# DotPhat.net
KiCad netlist of a schematic drawn in EAGLE
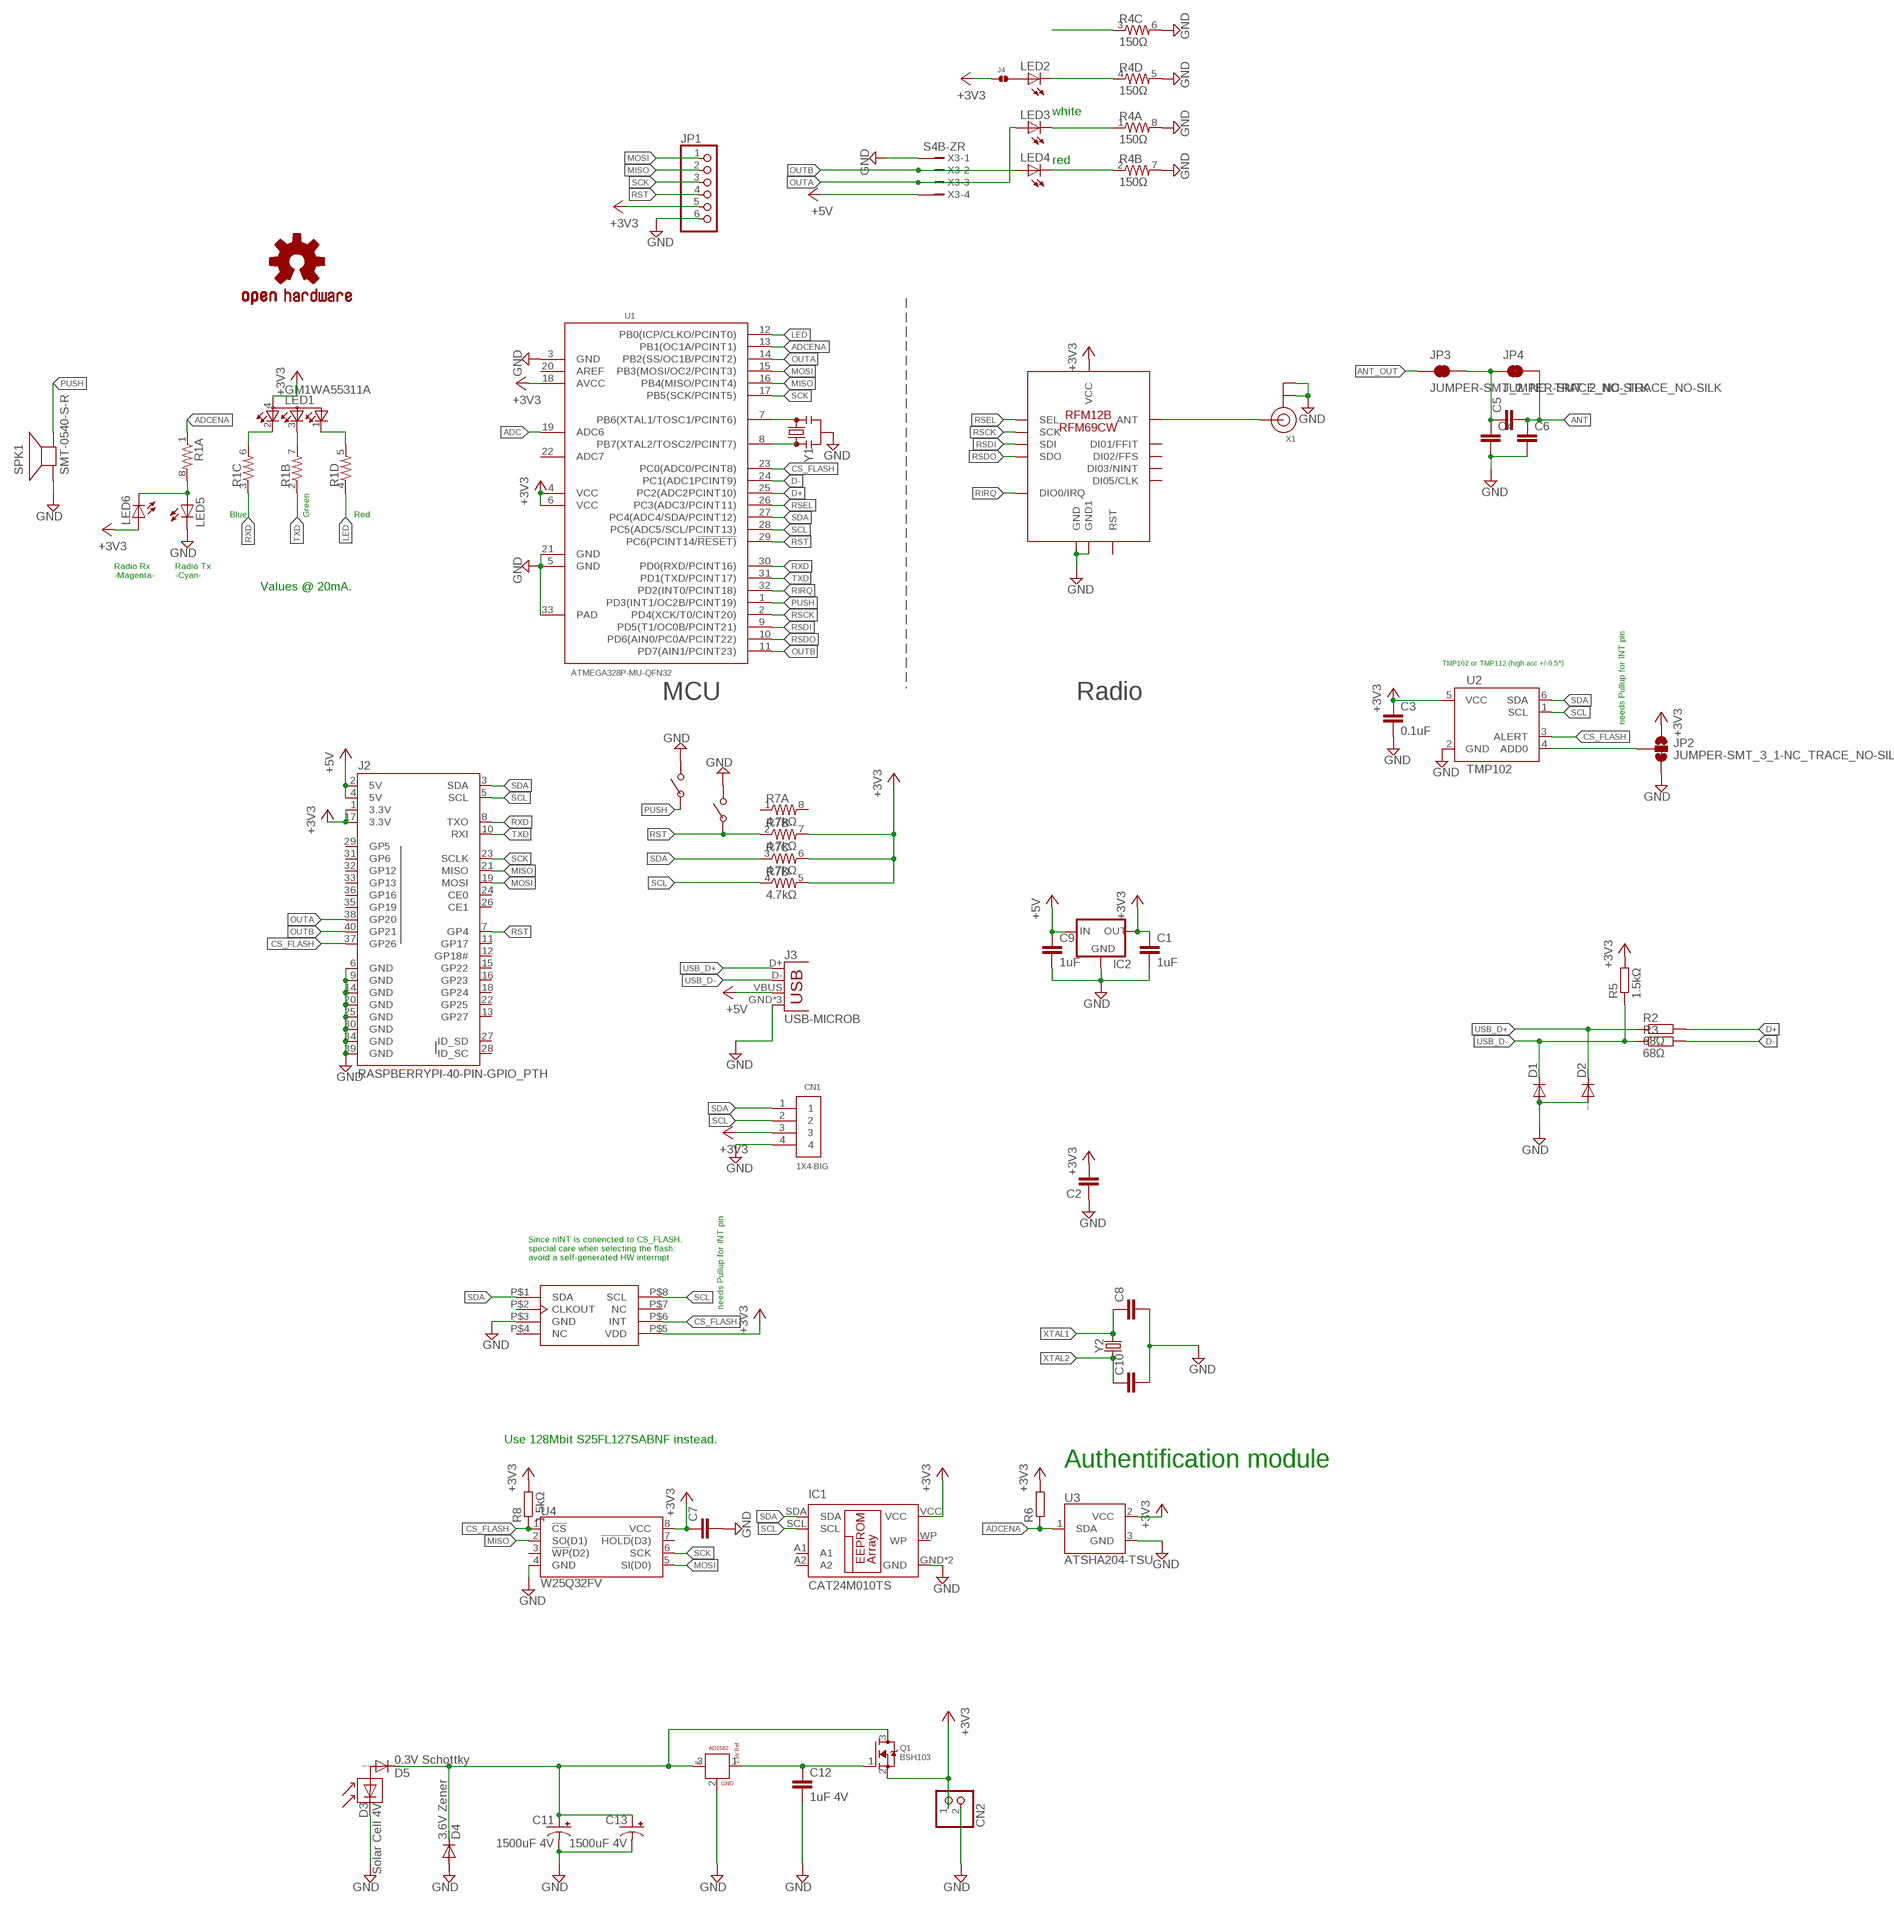
[diagram p0: schematic, sheet 1]

(export (version "E")
  (design (tool "Eeschema 10.0.6"))
  (components
    (comp (ref "C1")
      (value "1uF")
      (footprint "eagle-import:C0603")
      (libsource (lib "eagle-import") (part "C-EUC0603"))
    )
    (comp (ref "C2")
      (value "C-EUC3216")
      (footprint "eagle-import:C3216")
      (libsource (lib "eagle-import") (part "C-EUC3216"))
    )
    (comp (ref "C3")
      (value "0.1uF")
      (footprint "eagle-import:C0603")
      (libsource (lib "eagle-import") (part "resistor_C-EUC0603"))
    )
    (comp (ref "C4")
      (value "C-EUC0603")
      (footprint "eagle-import:C0603")
      (libsource (lib "eagle-import") (part "C-EUC0603"))
    )
    (comp (ref "C5")
      (value "C-EUC0603")
      (footprint "eagle-import:C0603")
      (libsource (lib "eagle-import") (part "C-EUC0603"))
    )
    (comp (ref "C6")
      (value "C-EUC0603")
      (footprint "eagle-import:C0603")
      (libsource (lib "eagle-import") (part "C-EUC0603"))
    )
    (comp (ref "C7")
      (value "C-EUC0603")
      (footprint "eagle-import:C0603")
      (libsource (lib "eagle-import") (part "C-EUC0603"))
    )
    (comp (ref "C8")
      (value "C-EUC0402")
      (footprint "eagle-import:C0402")
      (libsource (lib "eagle-import") (part "C-EUC0402"))
    )
    (comp (ref "C9")
      (value "1uF")
      (footprint "eagle-import:C0603")
      (libsource (lib "eagle-import") (part "C-EUC0603"))
    )
    (comp (ref "C10")
      (value "C-EUC0402")
      (footprint "eagle-import:C0402")
      (libsource (lib "eagle-import") (part "C-EUC0402"))
    )
    (comp (ref "C11")
      (value "1500uF 4V")
      (footprint "eagle-import:CT7343")
      (libsource (lib "eagle-import") (part "CPOL-USCT7343"))
    )
    (comp (ref "C12")
      (value "1uF 4V")
      (footprint "eagle-import:C0603")
      (libsource (lib "eagle-import") (part "C-EUC0603"))
    )
    (comp (ref "C13")
      (value "1500uF 4V")
      (footprint "eagle-import:CT7343")
      (libsource (lib "eagle-import") (part "CPOL-USCT7343"))
    )
    (comp (ref "CN1")
      (value "1X4-BIG")
      (footprint "eagle-import:1X04-BIG")
      (libsource (lib "eagle-import") (part "1X4-BIG"))
    )
    (comp (ref "CN2")
      (value "JST_2PIN-SMT-RA")
      (footprint "eagle-import:JST-PH-2-SMT-RA")
      (libsource (lib "eagle-import") (part "JST_2PIN-SMT-RA"))
    )
    (comp (ref "D1")
      (value "DIODE-SOD523")
      (footprint "eagle-import:SOD523")
      (libsource (lib "eagle-import") (part "DIODE-SOD523"))
    )
    (comp (ref "D2")
      (value "DIODE-SOD523")
      (footprint "eagle-import:SOD523")
      (libsource (lib "eagle-import") (part "DIODE-SOD523"))
    )
    (comp (ref "D3")
      (value "Solar Cell 4V")
      (footprint "eagle-import:SOLARBIT-12X1")
      (libsource (lib "eagle-import") (part "SOLAR-IXYS-"))
    )
    (comp (ref "D4")
      (value "3.6V Zener")
      (footprint "eagle-import:SOD523")
      (libsource (lib "eagle-import") (part "DIODE-SOD523"))
    )
    (comp (ref "D5")
      (value "0.3V Schottky")
      (footprint "eagle-import:SOD523")
      (libsource (lib "eagle-import") (part "DIODE-SOD523"))
    )
    (comp (ref "IC1")
      (value "CAT24M010TS")
      (footprint "eagle-import:TSSOP8")
      (fields (field (name "MF") "On Semiconductor") (field (name "MPN") "24C00T-E/ST"))
      (libsource (lib "eagle-import") (part "CAT24M01TS0"))
    )
    (comp (ref "IC2")
      (value "MCP1700TT")
      (footprint "eagle-import:SOT-23")
      (libsource (lib "eagle-import") (part "MCP1700TT"))
    )
    (comp (ref "J2")
      (value "RASPBERRYPI-40-PIN-GPIO_PTH")
      (footprint "eagle-import:2X20_SHROUDED")
      (libsource (lib "eagle-import") (part "RASPBERRYPI-40-PIN-GPIO_PTH"))
    )
    (comp (ref "J3")
      (value "USB-MICROB")
      (footprint "eagle-import:USB-MICROB")
      (libsource (lib "eagle-import") (part "USB-MICROB"))
    )
    (comp (ref "J4")
      (value "SOLDERJUMPER.2.MED")
      (footprint "eagle-import:2.MED")
      (libsource (lib "eagle-import") (part "SOLDERJUMPER.2.MED"))
    )
    (comp (ref "JP1")
      (value "PINHD-1X6")
      (footprint "eagle-import:1X06")
      (libsource (lib "eagle-import") (part "PINHD-1X6"))
    )
    (comp (ref "JP2")
      (value "JUMPER-SMT_3_1-NC_TRACE_NO-SILK")
      (footprint "eagle-import:SMT-JUMPER_3_1-NC_TRACE_NO-SILK")
      (libsource (lib "eagle-import") (part "JUMPER-SMT_3_1-NC_TRACE_NO-SILK"))
    )
    (comp (ref "JP3")
      (value "JUMPER-SMT_2_NC_TRACE_NO-SILK")
      (footprint "eagle-import:SMT-JUMPER_2_NC_TRACE_NO-SILK")
      (libsource (lib "eagle-import") (part "JUMPER-SMT_2_NC_TRACE_NO-SILK"))
    )
    (comp (ref "JP4")
      (value "JUMPER-SMT_2_NC_TRACE_NO-SILK")
      (footprint "eagle-import:SMT-JUMPER_2_NC_TRACE_NO-SILK")
      (libsource (lib "eagle-import") (part "JUMPER-SMT_2_NC_TRACE_NO-SILK"))
    )
    (comp (ref "LED1")
      (value "GM1WA55311A")
      (footprint "eagle-import:GM1WA55311A")
      (libsource (lib "eagle-import") (part "GM1WA55311A"))
    )
    (comp (ref "LED2")
      (value "LED0603")
      (footprint "eagle-import:LED-0603")
      (libsource (lib "eagle-import") (part "LED0603"))
    )
    (comp (ref "LED3")
      (value "LED0603")
      (footprint "eagle-import:LED-0603")
      (libsource (lib "eagle-import") (part "LED0603"))
    )
    (comp (ref "LED4")
      (value "LED0603")
      (footprint "eagle-import:LED-0603")
      (libsource (lib "eagle-import") (part "LED0603"))
    )
    (comp (ref "LED5")
      (value "LED0603")
      (footprint "eagle-import:LED-0603")
      (libsource (lib "eagle-import") (part "LED0603"))
    )
    (comp (ref "LED6")
      (value "LED0603")
      (footprint "eagle-import:LED-0603")
      (libsource (lib "eagle-import") (part "LED0603"))
    )
    (comp (ref "LOGO1")
      (value "OSHW-LOGOS")
      (footprint "eagle-import:OSHW-LOGO-S")
      (libsource (lib "eagle-import") (part "OSHW-LOGOS"))
    )
    (comp (ref "Q1")
      (value "BSH103")
      (footprint "eagle-import:SOT23")
      (libsource (lib "eagle-import") (part "MOSFET-NREFLOW"))
    )
    (comp (ref "R1")
      (value "RESISTOR-ARRAY0603-ARV")
      (footprint "eagle-import:0603-ARV")
      (libsource (lib "eagle-import") (part "RESISTOR-ARRAY0603-ARV"))
    )
    (comp (ref "R2")
      (value "68Ω")
      (footprint "eagle-import:R0603")
      (libsource (lib "eagle-import") (part "R-EU_R0603"))
    )
    (comp (ref "R3")
      (value "68Ω")
      (footprint "eagle-import:R0603")
      (libsource (lib "eagle-import") (part "R-EU_R0603"))
    )
    (comp (ref "R4")
      (value "150Ω")
      (footprint "eagle-import:0603-ARV")
      (libsource (lib "eagle-import") (part "RESISTOR-ARRAY0603-ARV"))
    )
    (comp (ref "R5")
      (value "1.5kΩ")
      (footprint "eagle-import:R0603")
      (libsource (lib "eagle-import") (part "R-EU_R0603"))
    )
    (comp (ref "R6")
      (value "R-EU_R0603")
      (footprint "eagle-import:R0603")
      (libsource (lib "eagle-import") (part "R-EU_R0603"))
    )
    (comp (ref "R7")
      (value "4.7kΩ")
      (footprint "eagle-import:0603-ARV")
      (libsource (lib "eagle-import") (part "RESISTOR-ARRAY0603-ARV"))
    )
    (comp (ref "R8")
      (value "1.5kΩ")
      (footprint "eagle-import:R0603")
      (libsource (lib "eagle-import") (part "R-EU_R0603"))
    )
    (comp (ref "SPK1")
      (value "SMT-0540-S-R")
      (footprint "eagle-import:SMT-0540-S-R")
      (libsource (lib "eagle-import") (part "SMT-0540-S-R"))
    )
    (comp (ref "U$1")
      (value "RFM12B/69CW")
      (footprint "eagle-import:RFM12B_69CW")
      (libsource (lib "eagle-import") (part "RFM12B/69CW"))
    )
    (comp (ref "U$2")
      (value "PUSHBUTTON_4X2.5")
      (footprint "eagle-import:PUSHBUTTON_4X2.5")
      (libsource (lib "eagle-import") (part "PUSHBUTTON_4X2.5"))
    )
    (comp (ref "U$3")
      (value "PUSHBUTTON_4X2.5")
      (footprint "eagle-import:PUSHBUTTON_4X2.5")
      (libsource (lib "eagle-import") (part "PUSHBUTTON_4X2.5"))
    )
    (comp (ref "U$4")
      (value "AD1582")
      (footprint "eagle-import:SOT23")
      (libsource (lib "eagle-import") (part "AD1582"))
    )
    (comp (ref "U1")
      (value "ATMEGA328P-MU-QFN32")
      (footprint "eagle-import:QFN32G-0.5-5X5MM")
      (fields (field (name "MPN") "ATMEGA328P-MU"))
      (libsource (lib "eagle-import") (part "MCU-ATMEGA328P-MU(QFN32)"))
    )
    (comp (ref "U2")
      (value "TMP102")
      (footprint "eagle-import:SOT563")
      (libsource (lib "eagle-import") (part "TMP102"))
    )
    (comp (ref "U3")
      (value "ATSHA204-TSU")
      (footprint "eagle-import:SOT23-3")
      (libsource (lib "eagle-import") (part "ATSHA204-TSU"))
    )
    (comp (ref "U4")
      (value "W25Q32FV")
      (footprint "eagle-import:WSON8-6X5MM")
      (libsource (lib "eagle-import") (part "W25Q32FVZP"))
    )
    (comp (ref "X1")
      (value "ANTENNA_U.FL")
      (footprint "eagle-import:U.FL")
      (libsource (lib "eagle-import") (part "ANTENNA_U.FL"))
    )
    (comp (ref "X2")
      (value "MC-RTC-RV-4162-C7-I2C")
      (footprint "eagle-import:MC-RTC-C7")
      (libsource (lib "eagle-import") (part "MC-RTC-RV-4162-C7-I2C"))
    )
    (comp (ref "X3")
      (value "S4B-ZR")
      (footprint "eagle-import:S4B-ZR")
      (fields (field (name "MF") "FARNELL") (field (name "MPN") "S4B-ZR(LF)(SN)"))
      (libsource (lib "eagle-import") (part "?4B-ZRS"))
    )
    (comp (ref "Y1")
      (value "RESONATORSMD-3.2X1.3")
      (footprint "eagle-import:RESONATOR-SMD-3.2X1.3")
      (libsource (lib "eagle-import") (part "RESONATORSMD-3.2X1.3"))
    )
    (comp (ref "Y2")
      (value "CRYSTALSMD-3.2X1.5")
      (footprint "eagle-import:CRYSTAL-SMD-3.2X1.5MM")
      (libsource (lib "eagle-import") (part "CRYSTALSMD-3.2X1.5"))
    )
  )
  (nets
    (net (code "1") (name "+3V3") (class "Default")
      (node (ref "C1") (pin "1") (pinfunction "1_1") (pintype "passive"))
      (node (ref "C2") (pin "2") (pinfunction "2_2") (pintype "passive"))
      (node (ref "C3") (pin "1") (pinfunction "1_1") (pintype "passive"))
      (node (ref "C7") (pin "1") (pinfunction "1_1") (pintype "passive"))
      (node (ref "CN1") (pin "3") (pinfunction "3_3") (pintype "bidirectional"))
      (node (ref "CN2") (pin "1") (pinfunction "2_1") (pintype "passive"))
      (node (ref "IC1") (pin "VCC") (pinfunction "VCC_VCC") (pintype "power_in"))
      (node (ref "IC2") (pin "2") (pinfunction "OUT_2") (pintype "passive"))
      (node (ref "J2") (pin "1") (pinfunction "3.3V_1") (pintype "power_in"))
      (node (ref "J2") (pin "17") (pinfunction "3.3V_17") (pintype "power_in"))
      (node (ref "J4") (pin "1") (pinfunction "1_1") (pintype "bidirectional"))
      (node (ref "JP1") (pin "5") (pinfunction "5_5") (pintype "passive"))
      (node (ref "JP2") (pin "1") (pinfunction "1_1") (pintype "passive"))
      (node (ref "LED1") (pin "4") (pinfunction "A_4") (pintype "passive"))
      (node (ref "LED6") (pin "A") (pinfunction "A_A") (pintype "passive"))
      (node (ref "Q1") (pin "2") (pinfunction "S_2") (pintype "bidirectional"))
      (node (ref "R5") (pin "2") (pinfunction "2_2") (pintype "passive"))
      (node (ref "R6") (pin "2") (pinfunction "2_2") (pintype "passive"))
      (node (ref "R7") (pin "5") (pinfunction "2_5") (pintype "passive"))
      (node (ref "R7") (pin "6") (pinfunction "2_6") (pintype "passive"))
      (node (ref "R7") (pin "7") (pinfunction "2_7") (pintype "passive"))
      (node (ref "R8") (pin "2") (pinfunction "2_2") (pintype "passive"))
      (node (ref "U$1") (pin "VDD") (pinfunction "VCC_VDD") (pintype "power_in"))
      (node (ref "U1") (pin "18") (pinfunction "AVCC_18") (pintype "bidirectional"))
      (node (ref "U1") (pin "4") (pinfunction "VCC_4") (pintype "bidirectional"))
      (node (ref "U1") (pin "6") (pinfunction "VCC_6") (pintype "bidirectional"))
      (node (ref "U2") (pin "5") (pinfunction "VCC_5") (pintype "bidirectional"))
      (node (ref "U3") (pin "2") (pinfunction "VCC_2") (pintype "bidirectional"))
      (node (ref "U4") (pin "8") (pinfunction "VCC_8") (pintype "bidirectional"))
      (node (ref "X2") (pin "P$5") (pinfunction "VDD_P$5") (pintype "power_in"))
    )
    (net (code "2") (name "+5V") (class "Default")
      (node (ref "C9") (pin "1") (pinfunction "1_1") (pintype "passive"))
      (node (ref "IC2") (pin "3") (pinfunction "IN_3") (pintype "input"))
      (node (ref "J2") (pin "2") (pinfunction "5V_2") (pintype "power_in"))
      (node (ref "J2") (pin "4") (pinfunction "5V_4") (pintype "power_in"))
      (node (ref "J3") (pin "VBUS") (pinfunction "VBUS_VBUS") (pintype "bidirectional"))
      (node (ref "X3") (pin "4") (pinfunction "1_4") (pintype "passive"))
    )
    (net (code "3") (name "ADC") (class "Default")
      (node (ref "U1") (pin "19") (pinfunction "ADC6_19") (pintype "bidirectional"))
    )
    (net (code "4") (name "ADCENA") (class "Default")
      (node (ref "R1") (pin "1") (pinfunction "1_1") (pintype "passive"))
      (node (ref "R6") (pin "1") (pinfunction "1_1") (pintype "passive"))
      (node (ref "U1") (pin "13") (pinfunction "PB1(OC1A/PCINT1)_13") (pintype "bidirectional"))
      (node (ref "U3") (pin "1") (pinfunction "SDA_1") (pintype "bidirectional"))
    )
    (net (code "5") (name "ANT") (class "Default")
      (node (ref "C5") (pin "2") (pinfunction "2_2") (pintype "passive"))
      (node (ref "C6") (pin "1") (pinfunction "1_1") (pintype "passive"))
      (node (ref "JP4") (pin "2") (pinfunction "2_2") (pintype "passive"))
    )
    (net (code "6") (name "ANT_OUT") (class "Default")
      (node (ref "JP3") (pin "1") (pinfunction "1_1") (pintype "passive"))
      (node (ref "U$1") (pin "ANT") (pinfunction "ANT_ANT") (pintype "passive"))
      (node (ref "X1") (pin "3") (pinfunction "SIGNAL_3") (pintype "passive"))
    )
    (net (code "7") (name "CS_FLASH") (class "Default")
      (node (ref "J2") (pin "37") (pinfunction "GP26_37") (pintype "bidirectional"))
      (node (ref "R8") (pin "1") (pinfunction "1_1") (pintype "passive"))
      (node (ref "U1") (pin "23") (pinfunction "PC0(ADC0/PCINT8)_23") (pintype "bidirectional"))
      (node (ref "U2") (pin "3") (pinfunction "ALERT_3") (pintype "bidirectional"))
      (node (ref "U4") (pin "1") (pinfunction "~{CS}_1") (pintype "bidirectional"))
      (node (ref "X2") (pin "P$6") (pinfunction "INT_P$6") (pintype "bidirectional"))
    )
    (net (code "8") (name "D+") (class "Default")
      (node (ref "R2") (pin "2") (pinfunction "2_2") (pintype "passive"))
      (node (ref "U1") (pin "25") (pinfunction "PC2(ADC2PCINT10)_25") (pintype "bidirectional"))
    )
    (net (code "9") (name "D-") (class "Default")
      (node (ref "R3") (pin "2") (pinfunction "2_2") (pintype "passive"))
      (node (ref "U1") (pin "24") (pinfunction "PC1(ADC1PCINT9)_24") (pintype "bidirectional"))
    )
    (net (code "10") (name "GND") (class "Default")
      (node (ref "C1") (pin "2") (pinfunction "2_2") (pintype "passive"))
      (node (ref "C10") (pin "2") (pinfunction "2_2") (pintype "passive"))
      (node (ref "C11") (pin "-") (pinfunction "-_-") (pintype "passive"))
      (node (ref "C12") (pin "2") (pinfunction "2_2") (pintype "passive"))
      (node (ref "C13") (pin "-") (pinfunction "-_-") (pintype "passive"))
      (node (ref "C2") (pin "1") (pinfunction "1_1") (pintype "passive"))
      (node (ref "C3") (pin "2") (pinfunction "2_2") (pintype "passive"))
      (node (ref "C4") (pin "2") (pinfunction "2_2") (pintype "passive"))
      (node (ref "C6") (pin "2") (pinfunction "2_2") (pintype "passive"))
      (node (ref "C7") (pin "2") (pinfunction "2_2") (pintype "passive"))
      (node (ref "C8") (pin "2") (pinfunction "2_2") (pintype "passive"))
      (node (ref "C9") (pin "2") (pinfunction "2_2") (pintype "passive"))
      (node (ref "CN1") (pin "4") (pinfunction "4_4") (pintype "bidirectional"))
      (node (ref "CN2") (pin "2") (pinfunction "1_2") (pintype "passive"))
      (node (ref "D1") (pin "A") (pinfunction "A_A") (pintype "passive"))
      (node (ref "D2") (pin "A") (pinfunction "A_A") (pintype "passive"))
      (node (ref "D3") (pin "-") (pinfunction "C_-") (pintype "passive"))
      (node (ref "D4") (pin "A") (pinfunction "A_A") (pintype "passive"))
      (node (ref "IC1") (pin "GND") (pinfunction "GND_GND") (pintype "power_in"))
      (node (ref "IC1") (pin "NC") (pinfunction "GND_NC") (pintype "power_in"))
      (node (ref "IC2") (pin "1") (pinfunction "GND_1") (pintype "input"))
      (node (ref "J2") (pin "14") (pinfunction "GND_14") (pintype "power_in"))
      (node (ref "J2") (pin "20") (pinfunction "GND_20") (pintype "power_in"))
      (node (ref "J2") (pin "25") (pinfunction "GND_25") (pintype "power_in"))
      (node (ref "J2") (pin "30") (pinfunction "GND_30") (pintype "power_in"))
      (node (ref "J2") (pin "34") (pinfunction "GND_34") (pintype "power_in"))
      (node (ref "J2") (pin "39") (pinfunction "GND_39") (pintype "power_in"))
      (node (ref "J2") (pin "6") (pinfunction "GND_6") (pintype "power_in"))
      (node (ref "J2") (pin "9") (pinfunction "GND_9") (pintype "power_in"))
      (node (ref "J3") (pin "GND") (pinfunction "GND_GND") (pintype "bidirectional"))
      (node (ref "J3") (pin "MT1") (pinfunction "GND_MT1") (pintype "bidirectional"))
      (node (ref "J3") (pin "MT2") (pinfunction "GND_MT2") (pintype "bidirectional"))
      (node (ref "JP1") (pin "6") (pinfunction "6_6") (pintype "passive"))
      (node (ref "JP2") (pin "3") (pinfunction "3_3") (pintype "passive"))
      (node (ref "LED5") (pin "C") (pinfunction "C_C") (pintype "passive"))
      (node (ref "R4") (pin "5") (pinfunction "2_5") (pintype "passive"))
      (node (ref "R4") (pin "6") (pinfunction "2_6") (pintype "passive"))
      (node (ref "R4") (pin "7") (pinfunction "2_7") (pintype "passive"))
      (node (ref "R4") (pin "8") (pinfunction "2_8") (pintype "passive"))
      (node (ref "SPK1") (pin "-") (pinfunction "+_-") (pintype "passive"))
      (node (ref "U$1") (pin "GND") (pinfunction "GND_GND") (pintype "power_in"))
      (node (ref "U$1") (pin "GND1") (pinfunction "GND1_GND1") (pintype "power_in"))
      (node (ref "U$2") (pin "P$2") (pinfunction "P$2_P$2") (pintype "bidirectional"))
      (node (ref "U$3") (pin "P$2") (pinfunction "P$2_P$2") (pintype "bidirectional"))
      (node (ref "U$4") (pin "2") (pinfunction "P$2_2") (pintype "bidirectional"))
      (node (ref "U1") (pin "21") (pinfunction "GND_21") (pintype "bidirectional"))
      (node (ref "U1") (pin "3") (pinfunction "GND_3") (pintype "bidirectional"))
      (node (ref "U1") (pin "33") (pinfunction "PAD_33") (pintype "bidirectional"))
      (node (ref "U1") (pin "5") (pinfunction "GND_5") (pintype "bidirectional"))
      (node (ref "U2") (pin "2") (pinfunction "GND_2") (pintype "bidirectional"))
      (node (ref "U3") (pin "3") (pinfunction "GND_3") (pintype "bidirectional"))
      (node (ref "U4") (pin "4") (pinfunction "GND_4") (pintype "bidirectional"))
      (node (ref "X1") (pin "1") (pinfunction "GND_1") (pintype "passive"))
      (node (ref "X1") (pin "2") (pinfunction "GND_2") (pintype "passive"))
      (node (ref "X2") (pin "P$3") (pinfunction "GND_P$3") (pintype "power_in"))
      (node (ref "X3") (pin "1") (pinfunction "1_1") (pintype "passive"))
      (node (ref "Y1") (pin "2") (pinfunction "2_2") (pintype "passive"))
    )
    (net (code "11") (name "LED") (class "Default")
      (node (ref "R1") (pin "4") (pinfunction "1_4") (pintype "passive"))
      (node (ref "U1") (pin "12") (pinfunction "PB0(ICP/CLKO/PCINT0)_12") (pintype "bidirectional"))
    )
    (net (code "12") (name "MISO") (class "Default")
      (node (ref "J2") (pin "21") (pinfunction "MISO_21") (pintype "input"))
      (node (ref "JP1") (pin "2") (pinfunction "2_2") (pintype "passive"))
      (node (ref "U1") (pin "16") (pinfunction "PB4(MISO/PCINT4)_16") (pintype "bidirectional"))
      (node (ref "U4") (pin "2") (pinfunction "SO(D1)_2") (pintype "bidirectional"))
    )
    (net (code "13") (name "MOSI") (class "Default")
      (node (ref "J2") (pin "19") (pinfunction "MOSI_19") (pintype "output"))
      (node (ref "JP1") (pin "1") (pinfunction "1_1") (pintype "passive"))
      (node (ref "U1") (pin "15") (pinfunction "PB3(MOSI/OC2/PCINT3)_15") (pintype "bidirectional"))
      (node (ref "U4") (pin "5") (pinfunction "SI(D0)_5") (pintype "bidirectional"))
    )
    (net (code "14") (name "Net-(C4-Pad1)") (class "Default")
      (node (ref "C4") (pin "1") (pinfunction "1_1") (pintype "passive"))
      (node (ref "C5") (pin "1") (pinfunction "1_1") (pintype "passive"))
      (node (ref "JP3") (pin "2") (pinfunction "2_2") (pintype "passive"))
      (node (ref "JP4") (pin "1") (pinfunction "1_1") (pintype "passive"))
    )
    (net (code "15") (name "Net-(D3-A)") (class "Default")
      (node (ref "D3") (pin "+") (pinfunction "A_+") (pintype "passive"))
      (node (ref "D5") (pin "A") (pinfunction "A_A") (pintype "passive"))
    )
    (net (code "16") (name "Net-(J4-Pad2)") (class "Default")
      (node (ref "J4") (pin "2") (pinfunction "2_2") (pintype "bidirectional"))
      (node (ref "LED2") (pin "A") (pinfunction "A_A") (pintype "passive"))
    )
    (net (code "17") (name "Net-(LED1-CBLUE)") (class "Default")
      (node (ref "LED1") (pin "3") (pinfunction "CBLUE_3") (pintype "passive"))
      (node (ref "R1") (pin "7") (pinfunction "2_7") (pintype "passive"))
    )
    (net (code "18") (name "Net-(LED1-CGREEN)") (class "Default")
      (node (ref "LED1") (pin "1") (pinfunction "CGREEN_1") (pintype "passive"))
      (node (ref "R1") (pin "5") (pinfunction "2_5") (pintype "passive"))
    )
    (net (code "19") (name "Net-(LED1-CRED)") (class "Default")
      (node (ref "LED1") (pin "2") (pinfunction "CRED_2") (pintype "passive"))
      (node (ref "R1") (pin "6") (pinfunction "2_6") (pintype "passive"))
    )
    (net (code "20") (name "Net-(LED3-PadC)") (class "Default")
      (node (ref "LED3") (pin "C") (pinfunction "C_C") (pintype "passive"))
      (node (ref "R4") (pin "1") (pinfunction "1_1") (pintype "passive"))
    )
    (net (code "21") (name "Net-(Q1-D)") (class "Default")
      (node (ref "C11") (pin "+") (pinfunction "+_+") (pintype "passive"))
      (node (ref "C13") (pin "+") (pinfunction "+_+") (pintype "passive"))
      (node (ref "D4") (pin "C") (pinfunction "C_C") (pintype "passive"))
      (node (ref "D5") (pin "C") (pinfunction "C_C") (pintype "passive"))
      (node (ref "Q1") (pin "3") (pinfunction "D_3") (pintype "bidirectional"))
      (node (ref "U$4") (pin "3") (pinfunction "P$3_3") (pintype "bidirectional"))
    )
    (net (code "22") (name "Net-(Q1-G)") (class "Default")
      (node (ref "C12") (pin "1") (pinfunction "1_1") (pintype "passive"))
      (node (ref "Q1") (pin "1") (pinfunction "G_1") (pintype "bidirectional"))
      (node (ref "U$4") (pin "1") (pinfunction "P$1_1") (pintype "bidirectional"))
    )
    (net (code "23") (name "Net-(R1A-2)") (class "Default")
      (node (ref "LED5") (pin "A") (pinfunction "A_A") (pintype "passive"))
      (node (ref "LED6") (pin "C") (pinfunction "C_C") (pintype "passive"))
      (node (ref "R1") (pin "8") (pinfunction "2_8") (pintype "passive"))
    )
    (net (code "24") (name "Net-(R4B-1)") (class "Default")
      (node (ref "LED4") (pin "C") (pinfunction "C_C") (pintype "passive"))
      (node (ref "R4") (pin "2") (pinfunction "1_2") (pintype "passive"))
    )
    (net (code "25") (name "Net-(R4D-1)") (class "Default")
      (node (ref "LED2") (pin "C") (pinfunction "C_C") (pintype "passive"))
      (node (ref "R4") (pin "4") (pinfunction "1_4") (pintype "passive"))
    )
    (net (code "26") (name "Net-(U1-PB6(XTAL1{slash}TOSC1{slash}PCINT6))") (class "Default")
      (node (ref "U1") (pin "7") (pinfunction "PB6(XTAL1/TOSC1/PCINT6)_7") (pintype "bidirectional"))
      (node (ref "Y1") (pin "3") (pinfunction "3_3") (pintype "passive"))
    )
    (net (code "27") (name "Net-(U1-PB7(XTAL2{slash}TOSC2{slash}PCINT7))") (class "Default")
      (node (ref "U1") (pin "8") (pinfunction "PB7(XTAL2/TOSC2/PCINT7)_8") (pintype "bidirectional"))
      (node (ref "Y1") (pin "1") (pinfunction "1_1") (pintype "passive"))
    )
    (net (code "28") (name "Net-(U2-ADD0)") (class "Default")
      (node (ref "JP2") (pin "2") (pinfunction "2_2") (pintype "passive"))
      (node (ref "U2") (pin "4") (pinfunction "ADD0_4") (pintype "bidirectional"))
    )
    (net (code "29") (name "OUTA") (class "Default")
      (node (ref "J2") (pin "38") (pinfunction "GP20_38") (pintype "bidirectional"))
      (node (ref "LED3") (pin "A") (pinfunction "A_A") (pintype "passive"))
      (node (ref "U1") (pin "14") (pinfunction "PB2(SS/OC1B/PCINT2)_14") (pintype "bidirectional"))
      (node (ref "X3") (pin "3") (pinfunction "1_3") (pintype "passive"))
    )
    (net (code "30") (name "OUTB") (class "Default")
      (node (ref "J2") (pin "40") (pinfunction "GP21_40") (pintype "bidirectional"))
      (node (ref "LED4") (pin "A") (pinfunction "A_A") (pintype "passive"))
      (node (ref "U1") (pin "11") (pinfunction "PD7(AIN1/PCINT23)_11") (pintype "bidirectional"))
      (node (ref "X3") (pin "2") (pinfunction "1_2") (pintype "passive"))
    )
    (net (code "31") (name "PUSH") (class "Default")
      (node (ref "SPK1") (pin "+") (pinfunction "-_+") (pintype "passive"))
      (node (ref "U$3") (pin "P$1") (pinfunction "P$1_P$1") (pintype "bidirectional"))
      (node (ref "U1") (pin "1") (pinfunction "PD3(INT1/OC2B/PCINT19)_1") (pintype "bidirectional"))
    )
    (net (code "32") (name "RIRQ") (class "Default")
      (node (ref "U$1") (pin "IRQ") (pinfunction "DIO0/IRQ_IRQ") (pintype "open_collector"))
      (node (ref "U1") (pin "32") (pinfunction "PD2(INT0/PCINT18)_32") (pintype "bidirectional"))
    )
    (net (code "33") (name "RSCK") (class "Default")
      (node (ref "U$1") (pin "SCK") (pinfunction "SCK_SCK") (pintype "input"))
      (node (ref "U1") (pin "2") (pinfunction "PD4(XCK/T0/CINT20)_2") (pintype "bidirectional"))
    )
    (net (code "34") (name "RSDI") (class "Default")
      (node (ref "U$1") (pin "SDI") (pinfunction "SDI_SDI") (pintype "input"))
      (node (ref "U1") (pin "9") (pinfunction "PD5(T1/OC0B/PCINT21)_9") (pintype "bidirectional"))
    )
    (net (code "35") (name "RSDO") (class "Default")
      (node (ref "U$1") (pin "SDO") (pinfunction "SDO_SDO") (pintype "output"))
      (node (ref "U1") (pin "10") (pinfunction "PD6(AIN0/PC0A/PCINT22)_10") (pintype "bidirectional"))
    )
    (net (code "36") (name "RSEL") (class "Default")
      (node (ref "U$1") (pin "SEL") (pinfunction "SEL_SEL") (pintype "input"))
      (node (ref "U1") (pin "26") (pinfunction "PC3(ADC3/PCINT11)_26") (pintype "bidirectional"))
    )
    (net (code "37") (name "RST") (class "Default")
      (node (ref "J2") (pin "7") (pinfunction "GP4_7") (pintype "bidirectional"))
      (node (ref "JP1") (pin "4") (pinfunction "4_4") (pintype "passive"))
      (node (ref "R7") (pin "2") (pinfunction "1_2") (pintype "passive"))
      (node (ref "U$2") (pin "P$1") (pinfunction "P$1_P$1") (pintype "bidirectional"))
      (node (ref "U1") (pin "29") (pinfunction "PC6(PCINT14/~{RESET})_29") (pintype "bidirectional"))
    )
    (net (code "38") (name "RXD") (class "Default")
      (node (ref "J2") (pin "8") (pinfunction "TXO_8") (pintype "output"))
      (node (ref "R1") (pin "3") (pinfunction "1_3") (pintype "passive"))
      (node (ref "U1") (pin "30") (pinfunction "PD0(RXD/PCINT16)_30") (pintype "bidirectional"))
    )
    (net (code "39") (name "SCK") (class "Default")
      (node (ref "J2") (pin "23") (pinfunction "SCLK_23") (pintype "output"))
      (node (ref "JP1") (pin "3") (pinfunction "3_3") (pintype "passive"))
      (node (ref "U1") (pin "17") (pinfunction "PB5(SCK/PCINT5)_17") (pintype "bidirectional"))
      (node (ref "U4") (pin "6") (pinfunction "SCK_6") (pintype "bidirectional"))
    )
    (net (code "40") (name "SCL") (class "Default")
      (node (ref "CN1") (pin "2") (pinfunction "2_2") (pintype "bidirectional"))
      (node (ref "IC1") (pin "SCL") (pinfunction "SCL_SCL") (pintype "input"))
      (node (ref "J2") (pin "5") (pinfunction "SCL_5") (pintype "bidirectional"))
      (node (ref "R7") (pin "4") (pinfunction "1_4") (pintype "passive"))
      (node (ref "U1") (pin "28") (pinfunction "PC5(ADC5/SCL/PCINT13)_28") (pintype "bidirectional"))
      (node (ref "U2") (pin "1") (pinfunction "SCL_1") (pintype "bidirectional"))
      (node (ref "X2") (pin "P$8") (pinfunction "SCL_P$8") (pintype "bidirectional"))
    )
    (net (code "41") (name "SDA") (class "Default")
      (node (ref "CN1") (pin "1") (pinfunction "1_1") (pintype "bidirectional"))
      (node (ref "IC1") (pin "SDA") (pinfunction "SDA_SDA") (pintype "bidirectional"))
      (node (ref "J2") (pin "3") (pinfunction "SDA_3") (pintype "bidirectional"))
      (node (ref "R7") (pin "3") (pinfunction "1_3") (pintype "passive"))
      (node (ref "U1") (pin "27") (pinfunction "PC4(ADC4/SDA/PCINT12)_27") (pintype "bidirectional"))
      (node (ref "U2") (pin "6") (pinfunction "SDA_6") (pintype "bidirectional"))
      (node (ref "X2") (pin "P$1") (pinfunction "SDA_P$1") (pintype "bidirectional"))
    )
    (net (code "42") (name "TXD") (class "Default")
      (node (ref "J2") (pin "10") (pinfunction "RXI_10") (pintype "input"))
      (node (ref "R1") (pin "2") (pinfunction "1_2") (pintype "passive"))
      (node (ref "U1") (pin "31") (pinfunction "PD1(TXD/PCINT17)_31") (pintype "bidirectional"))
    )
    (net (code "43") (name "USB_D+") (class "Default")
      (node (ref "D2") (pin "C") (pinfunction "C_C") (pintype "passive"))
      (node (ref "J3") (pin "D+") (pinfunction "D+_D+") (pintype "bidirectional"))
      (node (ref "R2") (pin "1") (pinfunction "1_1") (pintype "passive"))
    )
    (net (code "44") (name "USB_D-") (class "Default")
      (node (ref "D1") (pin "C") (pinfunction "C_C") (pintype "passive"))
      (node (ref "J3") (pin "D-") (pinfunction "D-_D-") (pintype "bidirectional"))
      (node (ref "R3") (pin "1") (pinfunction "1_1") (pintype "passive"))
      (node (ref "R5") (pin "1") (pinfunction "1_1") (pintype "passive"))
    )
    (net (code "45") (name "XTAL1") (class "Default")
      (node (ref "C8") (pin "1") (pinfunction "1_1") (pintype "passive"))
      (node (ref "Y2") (pin "P$2") (pinfunction "2_P$2") (pintype "passive"))
    )
    (net (code "46") (name "XTAL2") (class "Default")
      (node (ref "C10") (pin "1") (pinfunction "1_1") (pintype "passive"))
      (node (ref "Y2") (pin "P$1") (pinfunction "1_P$1") (pintype "passive"))
    )
    (net (code "47") (name "unconnected-(IC1-PadA1)") (class "Default")
      (node (ref "IC1") (pin "A1") (pinfunction "A1_A1") (pintype "bidirectional"))
    )
    (net (code "48") (name "unconnected-(IC1-PadA2)") (class "Default")
      (node (ref "IC1") (pin "A2") (pinfunction "A2_A2") (pintype "bidirectional"))
    )
    (net (code "49") (name "unconnected-(IC1-PadWP)") (class "Default")
      (node (ref "IC1") (pin "WP") (pinfunction "WP_WP") (pintype "bidirectional"))
    )
    (net (code "50") (name "unconnected-(J2-CE0-Pad24)") (class "Default")
      (node (ref "J2") (pin "24") (pinfunction "CE0_24") (pintype "output"))
    )
    (net (code "51") (name "unconnected-(J2-CE1-Pad26)") (class "Default")
      (node (ref "J2") (pin "26") (pinfunction "CE1_26") (pintype "output"))
    )
    (net (code "52") (name "unconnected-(J2-GP5-Pad29)") (class "Default")
      (node (ref "J2") (pin "29") (pinfunction "GP5_29") (pintype "bidirectional"))
    )
    (net (code "53") (name "unconnected-(J2-GP6-Pad31)") (class "Default")
      (node (ref "J2") (pin "31") (pinfunction "GP6_31") (pintype "bidirectional"))
    )
    (net (code "54") (name "unconnected-(J2-GP12-Pad32)") (class "Default")
      (node (ref "J2") (pin "32") (pinfunction "GP12_32") (pintype "bidirectional"))
    )
    (net (code "55") (name "unconnected-(J2-GP13-Pad33)") (class "Default")
      (node (ref "J2") (pin "33") (pinfunction "GP13_33") (pintype "bidirectional"))
    )
    (net (code "56") (name "unconnected-(J2-GP16-Pad36)") (class "Default")
      (node (ref "J2") (pin "36") (pinfunction "GP16_36") (pintype "bidirectional"))
    )
    (net (code "57") (name "unconnected-(J2-GP17-Pad11)") (class "Default")
      (node (ref "J2") (pin "11") (pinfunction "GP17_11") (pintype "bidirectional"))
    )
    (net (code "58") (name "unconnected-(J2-GP18#-Pad12)") (class "Default")
      (node (ref "J2") (pin "12") (pinfunction "GP18#_12") (pintype "bidirectional"))
    )
    (net (code "59") (name "unconnected-(J2-GP19-Pad35)") (class "Default")
      (node (ref "J2") (pin "35") (pinfunction "GP19_35") (pintype "bidirectional"))
    )
    (net (code "60") (name "unconnected-(J2-GP22-Pad15)") (class "Default")
      (node (ref "J2") (pin "15") (pinfunction "GP22_15") (pintype "bidirectional"))
    )
    (net (code "61") (name "unconnected-(J2-GP23-Pad16)") (class "Default")
      (node (ref "J2") (pin "16") (pinfunction "GP23_16") (pintype "bidirectional"))
    )
    (net (code "62") (name "unconnected-(J2-GP24-Pad18)") (class "Default")
      (node (ref "J2") (pin "18") (pinfunction "GP24_18") (pintype "bidirectional"))
    )
    (net (code "63") (name "unconnected-(J2-GP25-Pad22)") (class "Default")
      (node (ref "J2") (pin "22") (pinfunction "GP25_22") (pintype "bidirectional"))
    )
    (net (code "64") (name "unconnected-(J2-GP27-Pad13)") (class "Default")
      (node (ref "J2") (pin "13") (pinfunction "GP27_13") (pintype "bidirectional"))
    )
    (net (code "65") (name "unconnected-(J2-ID_SC-Pad28)") (class "Default")
      (node (ref "J2") (pin "28") (pinfunction "ID_SC_28") (pintype "bidirectional"))
    )
    (net (code "66") (name "unconnected-(J2-ID_SD-Pad27)") (class "Default")
      (node (ref "J2") (pin "27") (pinfunction "ID_SD_27") (pintype "bidirectional"))
    )
    (net (code "67") (name "unconnected-(R4C-1-Pad3)") (class "Default")
      (node (ref "R4") (pin "3") (pinfunction "1_3") (pintype "passive"))
    )
    (net (code "68") (name "unconnected-(R7-Pad1)") (class "Default")
      (node (ref "R7") (pin "1") (pinfunction "1_1") (pintype "passive"))
    )
    (net (code "69") (name "unconnected-(R7A-2-Pad8)") (class "Default")
      (node (ref "R7") (pin "8") (pinfunction "2_8") (pintype "passive"))
    )
    (net (code "70") (name "unconnected-(U$1-DI01{slash}FFIT-PadFFIT)") (class "Default")
      (node (ref "U$1") (pin "FFIT") (pinfunction "DI01/FFIT_FFIT") (pintype "passive"))
    )
    (net (code "71") (name "unconnected-(U$1-DI02{slash}FFS-PadFFS)") (class "Default")
      (node (ref "U$1") (pin "FFS") (pinfunction "DI02/FFS_FFS") (pintype "bidirectional"))
    )
    (net (code "72") (name "unconnected-(U$1-DI03{slash}NINT-PadNINT)") (class "Default")
      (node (ref "U$1") (pin "NINT") (pinfunction "DI03/NINT_NINT") (pintype "passive"))
    )
    (net (code "73") (name "unconnected-(U$1-DI05{slash}CLK-PadCLK)") (class "Default")
      (node (ref "U$1") (pin "CLK") (pinfunction "DI05/CLK_CLK") (pintype "passive"))
    )
    (net (code "74") (name "unconnected-(U$1-PadRST)") (class "Default")
      (node (ref "U$1") (pin "RST") (pinfunction "RST_RST") (pintype "open_collector"))
    )
    (net (code "75") (name "unconnected-(U1-ADC7-Pad22)") (class "Default")
      (node (ref "U1") (pin "22") (pinfunction "ADC7_22") (pintype "bidirectional"))
    )
    (net (code "76") (name "unconnected-(U1-AREF-Pad20)") (class "Default")
      (node (ref "U1") (pin "20") (pinfunction "AREF_20") (pintype "bidirectional"))
    )
    (net (code "77") (name "unconnected-(U4-~{HOLD}(D3)-Pad7)") (class "Default")
      (node (ref "U4") (pin "7") (pinfunction "~{HOLD}(D3)_7") (pintype "bidirectional"))
    )
    (net (code "78") (name "unconnected-(U4-~{WP}(D2)-Pad3)") (class "Default")
      (node (ref "U4") (pin "3") (pinfunction "~{WP}(D2)_3") (pintype "bidirectional"))
    )
    (net (code "79") (name "unconnected-(X2-CLKOUT-PadP$2)") (class "Default")
      (node (ref "X2") (pin "P$2") (pinfunction "CLKOUT_P$2") (pintype "bidirectional"))
    )
    (net (code "80") (name "unconnected-(X2-NC-PadP$4)") (class "Default")
      (node (ref "X2") (pin "P$4") (pinfunction "NC_P$4") (pintype "no_connect"))
    )
    (net (code "81") (name "unconnected-(X2-NC-PadP$7)") (class "Default")
      (node (ref "X2") (pin "P$7") (pinfunction "NC_P$7") (pintype "no_connect"))
    )
  )
)
